# psu.net
KiCad netlist of a schematic drawn in EAGLE
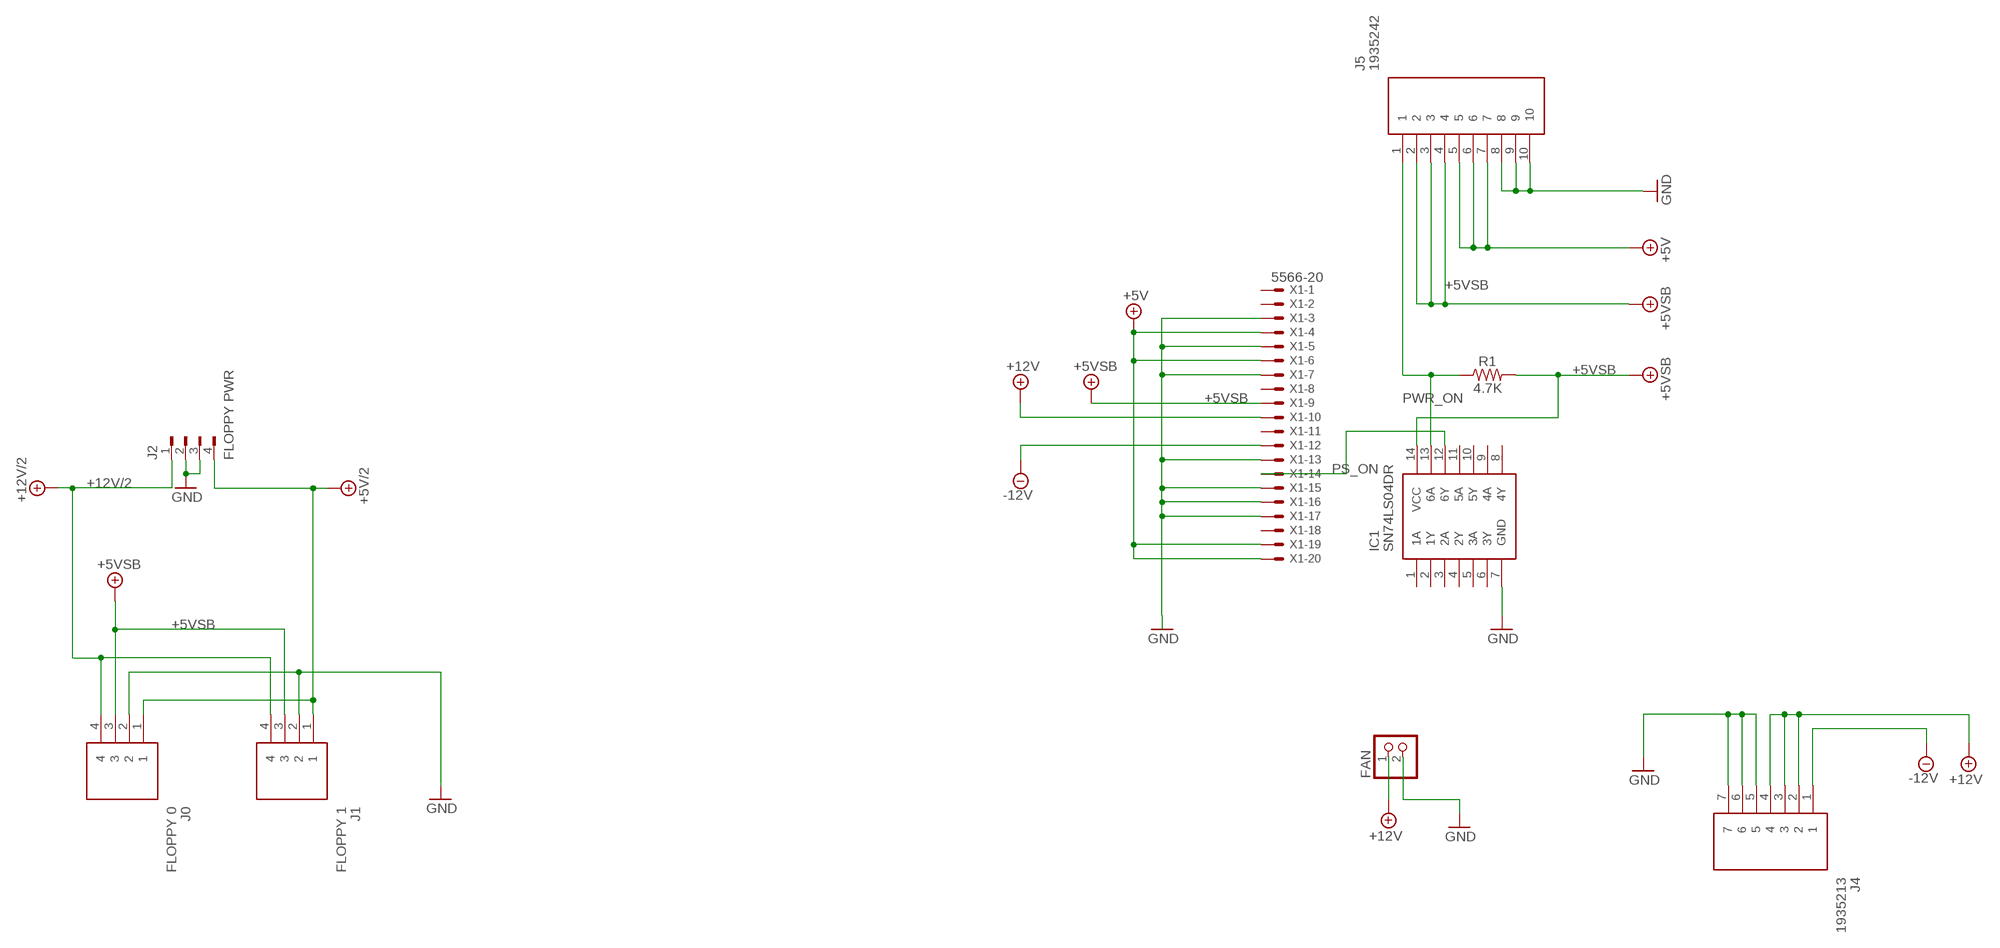
[diagram p0: schematic, sheet 1]

(export (version "E")
  (design (tool "Eeschema 10.0.6"))
  (components
    (comp (ref "FAN")
      (value "PINHD-1X2")
      (footprint "eagle-import:1X02")
      (libsource (lib "eagle-import") (part "PINHD-1X2"))
    )
    (comp (ref "IC1")
      (value "SN74LS04DR")
      (footprint "eagle-import:SOIC127P600X175-14N")
      (fields (field (name "MOUSER_PART_NUMBER") "595-SN74LS04DR"))
      (libsource (lib "eagle-import") (part "SN74LS04DR"))
    )
    (comp (ref "J0")
      (value "FLOPPY 0")
      (footprint "eagle-import:HDRV4W69P0X250_1X4_1000X500X10")
      (fields
        (field (name "MANUFACTURER_PART_NUMBER") "171825-4")
        (field (name "MOUSER_PART_NUMBER") "571-1718254")
      )
      (libsource (lib "eagle-import") (part "171825-4"))
    )
    (comp (ref "J1")
      (value "FLOPPY 1")
      (footprint "eagle-import:HDRV4W69P0X250_1X4_1000X500X10")
      (fields
        (field (name "MANUFACTURER_PART_NUMBER") "171825-4")
        (field (name "MOUSER_PART_NUMBER") "571-1718254")
      )
      (libsource (lib "eagle-import") (part "171825-4"))
    )
    (comp (ref "J2")
      (value "FLOPPY PWR")
      (footprint "eagle-import:350211")
      (libsource (lib "eagle-import") (part "FLOPPY-4350211"))
    )
    (comp (ref "J4")
      (value "1935213")
      (footprint "eagle-import:1935213")
      (fields (field (name "MOUSER_PART_NUMBER") "651-1935213"))
      (libsource (lib "eagle-import") (part "1935213"))
    )
    (comp (ref "J5")
      (value "1935242")
      (footprint "eagle-import:SHDR10W130P0X500_1X10_5000X850")
      (fields (field (name "MOUSER_PART_NUMBER") "651-1935242"))
      (libsource (lib "eagle-import") (part "1935242"))
    )
    (comp (ref "R1")
      (value "4.7K")
      (footprint "eagle-import:0805")
      (libsource (lib "eagle-import") (part "RESISTOR0805"))
    )
    (comp (ref "X1")
      (value "5566-20")
      (footprint "eagle-import:5566-20")
      (fields (field (name "MF") "MOLEX"))
      (libsource (lib "eagle-import") (part "5566-20"))
    )
  )
  (nets
    (net (code "1") (name "+5V") (class "Default")
      (node (ref "J5") (pin "5") (pinfunction "5_5") (pintype "bidirectional"))
      (node (ref "J5") (pin "6") (pinfunction "6_6") (pintype "bidirectional"))
      (node (ref "J5") (pin "7") (pinfunction "7_7") (pintype "bidirectional"))
      (node (ref "X1") (pin "19") (pinfunction "S_19") (pintype "passive"))
      (node (ref "X1") (pin "20") (pinfunction "S_20") (pintype "passive"))
      (node (ref "X1") (pin "4") (pinfunction "S_4") (pintype "passive"))
      (node (ref "X1") (pin "6") (pinfunction "S_6") (pintype "passive"))
    )
    (net (code "2") (name "+5VSB") (class "Default")
      (node (ref "IC1") (pin "14") (pinfunction "VCC_14") (pintype "bidirectional"))
      (node (ref "J0") (pin "3") (pinfunction "3_3") (pintype "bidirectional"))
      (node (ref "J1") (pin "3") (pinfunction "3_3") (pintype "bidirectional"))
      (node (ref "J5") (pin "2") (pinfunction "2_2") (pintype "bidirectional"))
      (node (ref "J5") (pin "3") (pinfunction "3_3") (pintype "bidirectional"))
      (node (ref "J5") (pin "4") (pinfunction "4_4") (pintype "bidirectional"))
      (node (ref "R1") (pin "2") (pinfunction "2_2") (pintype "passive"))
      (node (ref "X1") (pin "9") (pinfunction "S_9") (pintype "passive"))
    )
    (net (code "3") (name "+5V{slash}2") (class "Default")
      (node (ref "J0") (pin "1") (pinfunction "1_1") (pintype "bidirectional"))
      (node (ref "J1") (pin "1") (pinfunction "1_1") (pintype "bidirectional"))
      (node (ref "J2") (pin "4") (pinfunction "4_4") (pintype "passive"))
    )
    (net (code "4") (name "+12V") (class "Default")
      (node (ref "FAN") (pin "1") (pinfunction "1_1") (pintype "passive"))
      (node (ref "J4") (pin "2") (pinfunction "2_2") (pintype "bidirectional"))
      (node (ref "J4") (pin "3") (pinfunction "3_3") (pintype "bidirectional"))
      (node (ref "J4") (pin "4") (pinfunction "4_4") (pintype "bidirectional"))
      (node (ref "X1") (pin "10") (pinfunction "S_10") (pintype "passive"))
    )
    (net (code "5") (name "+12V{slash}2") (class "Default")
      (node (ref "J0") (pin "4") (pinfunction "4_4") (pintype "bidirectional"))
      (node (ref "J1") (pin "4") (pinfunction "4_4") (pintype "bidirectional"))
      (node (ref "J2") (pin "1") (pinfunction "1_1") (pintype "passive"))
    )
    (net (code "6") (name "-12V") (class "Default")
      (node (ref "J4") (pin "1") (pinfunction "1_1") (pintype "bidirectional"))
      (node (ref "X1") (pin "12") (pinfunction "S_12") (pintype "passive"))
    )
    (net (code "7") (name "/PS_ON") (class "Default")
      (node (ref "IC1") (pin "12") (pinfunction "6Y_12") (pintype "bidirectional"))
      (node (ref "X1") (pin "14") (pinfunction "S_14") (pintype "passive"))
    )
    (net (code "8") (name "/PWR_ON") (class "Default")
      (node (ref "IC1") (pin "13") (pinfunction "6A_13") (pintype "bidirectional"))
      (node (ref "J5") (pin "1") (pinfunction "1_1") (pintype "bidirectional"))
      (node (ref "R1") (pin "1") (pinfunction "1_1") (pintype "passive"))
    )
    (net (code "9") (name "GND") (class "Default")
      (node (ref "FAN") (pin "2") (pinfunction "2_2") (pintype "passive"))
      (node (ref "IC1") (pin "7") (pinfunction "GND_7") (pintype "bidirectional"))
      (node (ref "J0") (pin "2") (pinfunction "2_2") (pintype "bidirectional"))
      (node (ref "J1") (pin "2") (pinfunction "2_2") (pintype "bidirectional"))
      (node (ref "J2") (pin "2") (pinfunction "2_2") (pintype "passive"))
      (node (ref "J2") (pin "3") (pinfunction "3_3") (pintype "passive"))
      (node (ref "J4") (pin "5") (pinfunction "5_5") (pintype "bidirectional"))
      (node (ref "J4") (pin "6") (pinfunction "6_6") (pintype "bidirectional"))
      (node (ref "J4") (pin "7") (pinfunction "7_7") (pintype "bidirectional"))
      (node (ref "J5") (pin "10") (pinfunction "10_10") (pintype "bidirectional"))
      (node (ref "J5") (pin "8") (pinfunction "8_8") (pintype "bidirectional"))
      (node (ref "J5") (pin "9") (pinfunction "9_9") (pintype "bidirectional"))
      (node (ref "X1") (pin "13") (pinfunction "S_13") (pintype "passive"))
      (node (ref "X1") (pin "15") (pinfunction "S_15") (pintype "passive"))
      (node (ref "X1") (pin "16") (pinfunction "S_16") (pintype "passive"))
      (node (ref "X1") (pin "17") (pinfunction "S_17") (pintype "passive"))
      (node (ref "X1") (pin "3") (pinfunction "S_3") (pintype "passive"))
      (node (ref "X1") (pin "5") (pinfunction "S_5") (pintype "passive"))
      (node (ref "X1") (pin "7") (pinfunction "S_7") (pintype "passive"))
    )
    (net (code "10") (name "unconnected-(IC1-1A-Pad1)") (class "Default")
      (node (ref "IC1") (pin "1") (pinfunction "1A_1") (pintype "bidirectional"))
    )
    (net (code "11") (name "unconnected-(IC1-1Y-Pad2)") (class "Default")
      (node (ref "IC1") (pin "2") (pinfunction "1Y_2") (pintype "bidirectional"))
    )
    (net (code "12") (name "unconnected-(IC1-2A-Pad3)") (class "Default")
      (node (ref "IC1") (pin "3") (pinfunction "2A_3") (pintype "bidirectional"))
    )
    (net (code "13") (name "unconnected-(IC1-2Y-Pad4)") (class "Default")
      (node (ref "IC1") (pin "4") (pinfunction "2Y_4") (pintype "bidirectional"))
    )
    (net (code "14") (name "unconnected-(IC1-3A-Pad5)") (class "Default")
      (node (ref "IC1") (pin "5") (pinfunction "3A_5") (pintype "bidirectional"))
    )
    (net (code "15") (name "unconnected-(IC1-3Y-Pad6)") (class "Default")
      (node (ref "IC1") (pin "6") (pinfunction "3Y_6") (pintype "bidirectional"))
    )
    (net (code "16") (name "unconnected-(IC1-4A-Pad9)") (class "Default")
      (node (ref "IC1") (pin "9") (pinfunction "4A_9") (pintype "bidirectional"))
    )
    (net (code "17") (name "unconnected-(IC1-4Y-Pad8)") (class "Default")
      (node (ref "IC1") (pin "8") (pinfunction "4Y_8") (pintype "bidirectional"))
    )
    (net (code "18") (name "unconnected-(IC1-5A-Pad11)") (class "Default")
      (node (ref "IC1") (pin "11") (pinfunction "5A_11") (pintype "bidirectional"))
    )
    (net (code "19") (name "unconnected-(IC1-5Y-Pad10)") (class "Default")
      (node (ref "IC1") (pin "10") (pinfunction "5Y_10") (pintype "bidirectional"))
    )
    (net (code "20") (name "unconnected-(X1A-S-Pad1)") (class "Default")
      (node (ref "X1") (pin "1") (pinfunction "S_1") (pintype "passive"))
    )
    (net (code "21") (name "unconnected-(X1C-S-Pad11)") (class "Default")
      (node (ref "X1") (pin "11") (pinfunction "S_11") (pintype "passive"))
    )
    (net (code "22") (name "unconnected-(X1J-S-Pad18)") (class "Default")
      (node (ref "X1") (pin "18") (pinfunction "S_18") (pintype "passive"))
    )
    (net (code "23") (name "unconnected-(X1L-S-Pad2)") (class "Default")
      (node (ref "X1") (pin "2") (pinfunction "S_2") (pintype "passive"))
    )
    (net (code "24") (name "unconnected-(X1S-S-Pad8)") (class "Default")
      (node (ref "X1") (pin "8") (pinfunction "S_8") (pintype "passive"))
    )
  )
)
